# Pill_STM32F405.net
KiCad netlist of a schematic drawn in Altium Designer
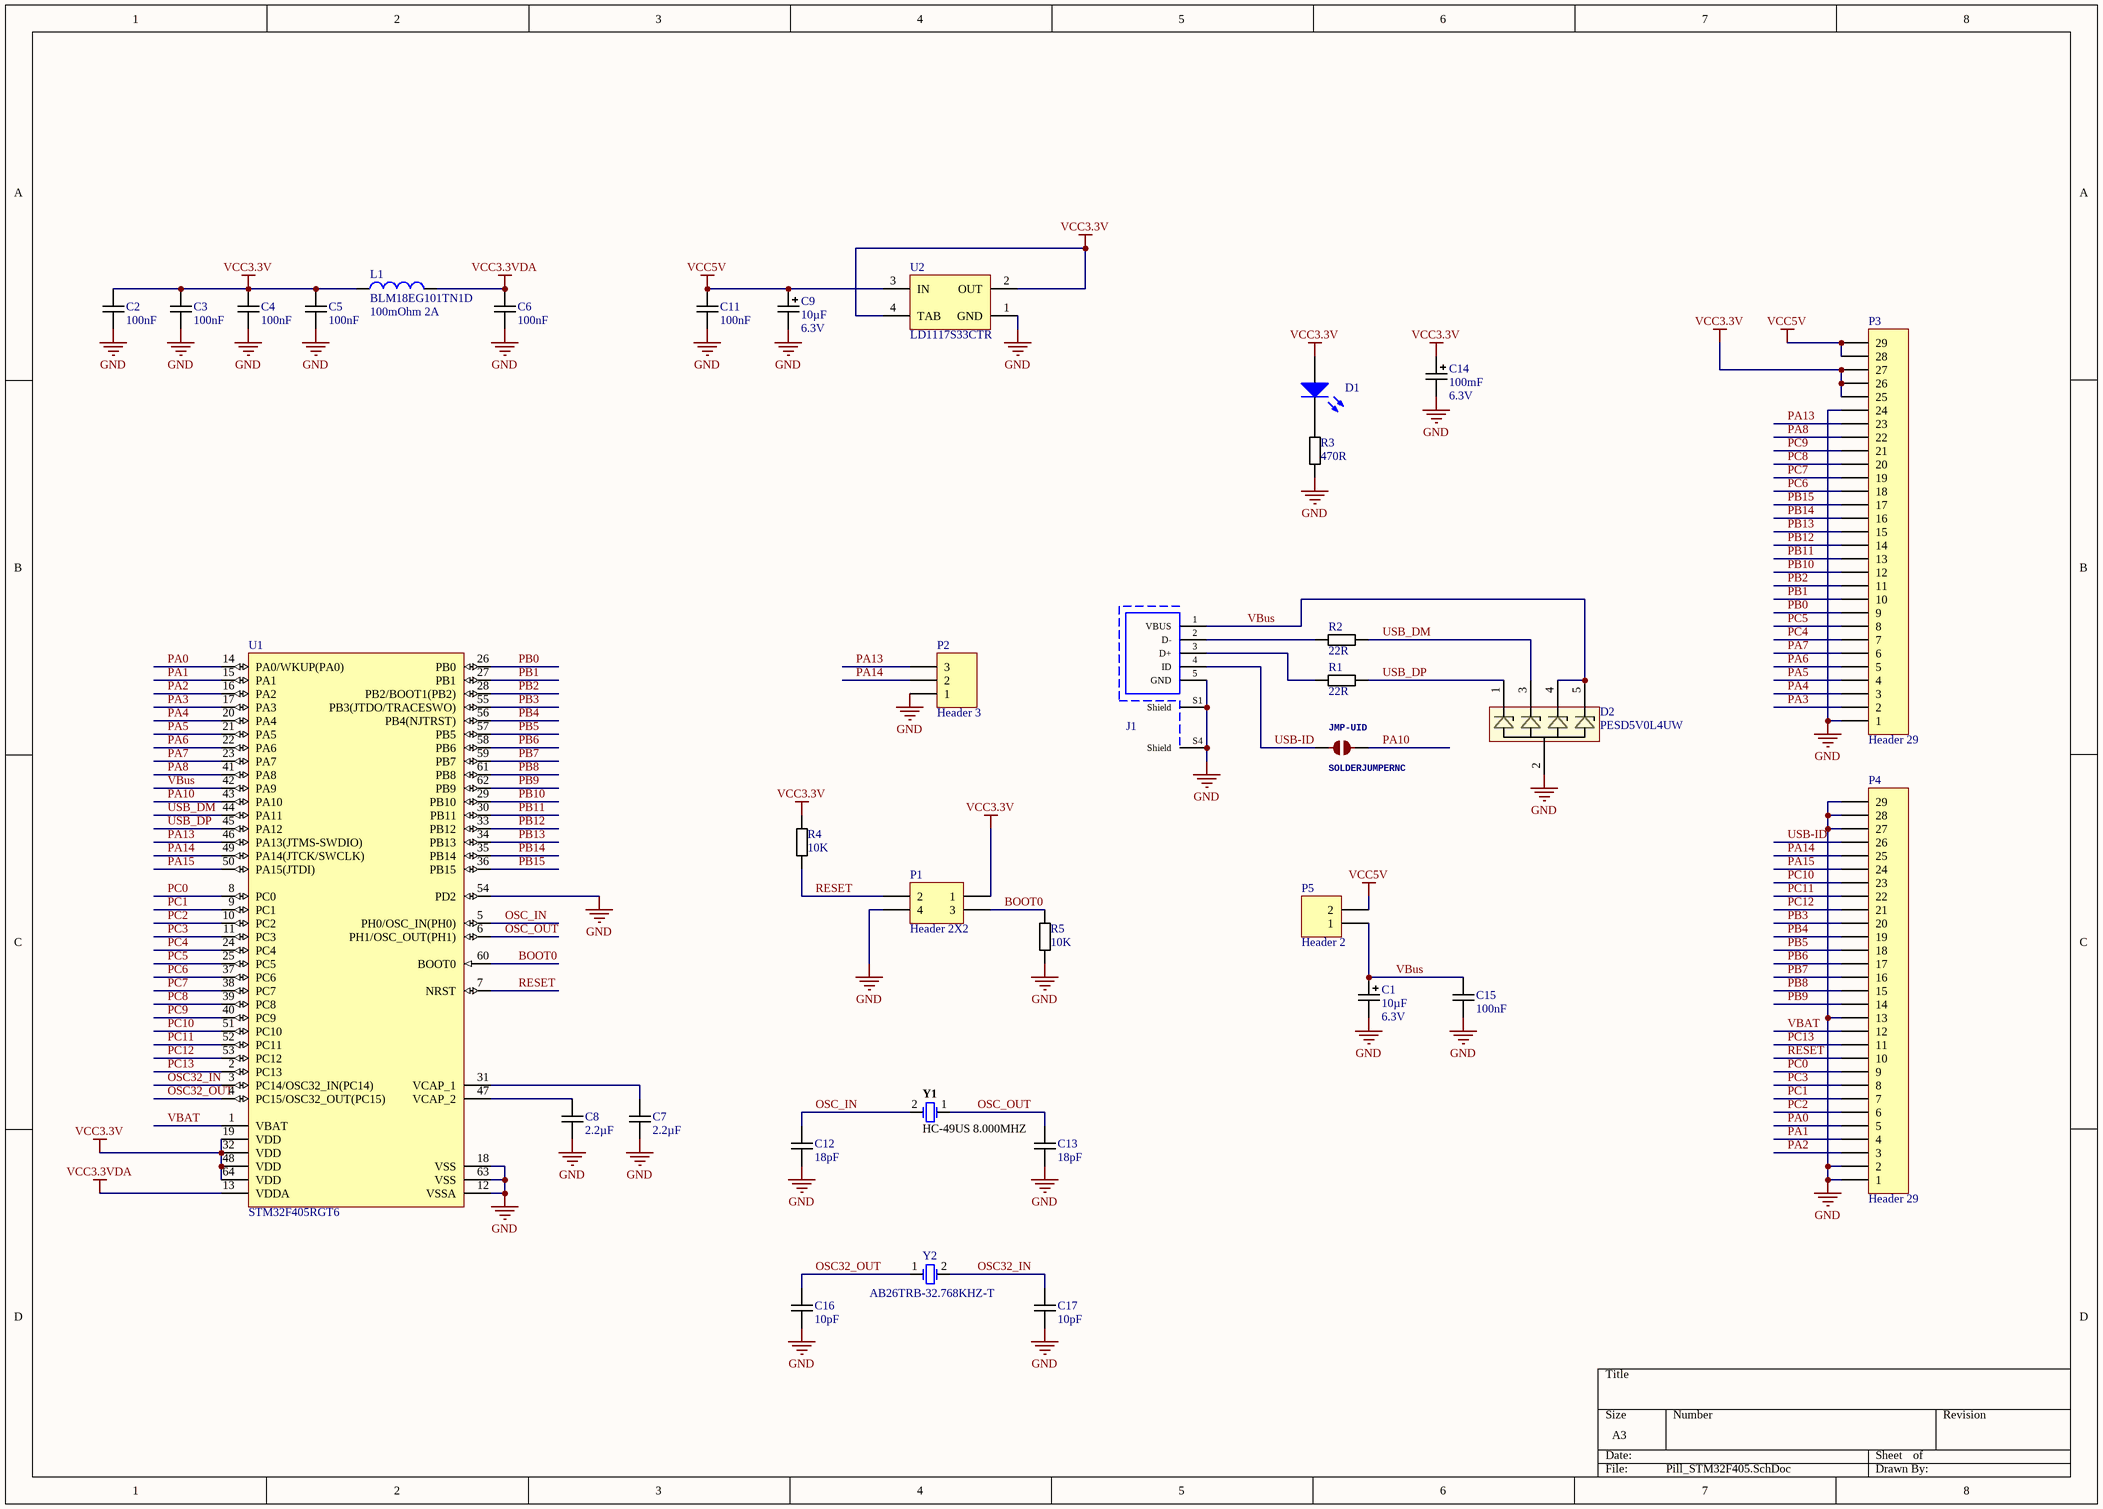
[diagram p0: Pill_STM32F405.SchDoc]

(export (version "E")
  (design (tool "Eeschema 10.0.6"))
  (components
    (comp (ref "C1")
      (value "10µF")
      (footprint "Capacitor_tantal_SMD:Body_A_M__CAPMP3216X18N")
      (description "10µF Molded Tantalum Capacitors 6.3V 1206 (3216 Metric) 4Ohm @ 100kHz")
      (fields
        (field (name "TOLERANCE") "5%")
        (field (name "MANUFACTURER") "AVX Corporation")
        (field (name "VOLTAGE - RATED") "6.3V")
      )
      (libsource (lib "Capacitors") (part "Capacitor Polarized"))
    )
    (comp (ref "C2")
      (value "100nF")
      (footprint "Pill_STM32F405:0603-CAP")
      (description "Capacitor 0603 100nF 50V")
      (fields (field (name "TOLERANCE") "±10%") (field (name "MANUFACTURER") "TDK Corporation"))
      (libsource (lib "Pill_STM32F405") (part "Capacitor_0603_100nF"))
    )
    (comp (ref "C3")
      (value "100nF")
      (footprint "Pill_STM32F405:0603-CAP")
      (description "Capacitor 0603 100nF 50V")
      (fields (field (name "TOLERANCE") "±10%") (field (name "MANUFACTURER") "TDK Corporation"))
      (libsource (lib "Pill_STM32F405") (part "Capacitor_0603_100nF"))
    )
    (comp (ref "C4")
      (value "100nF")
      (footprint "Pill_STM32F405:0603-CAP")
      (description "Capacitor 0603 100nF 50V")
      (fields (field (name "TOLERANCE") "±10%") (field (name "MANUFACTURER") "TDK Corporation"))
      (libsource (lib "Pill_STM32F405") (part "Capacitor_0603_100nF"))
    )
    (comp (ref "C5")
      (value "100nF")
      (footprint "Pill_STM32F405:0603-CAP")
      (description "Capacitor 0603 100nF 50V")
      (fields (field (name "TOLERANCE") "±10%") (field (name "MANUFACTURER") "TDK Corporation"))
      (libsource (lib "Pill_STM32F405") (part "Capacitor_0603_100nF"))
    )
    (comp (ref "C6")
      (value "100nF")
      (footprint "Pill_STM32F405:0603-CAP")
      (description "Capacitor 0603 100nF 50V")
      (fields (field (name "TOLERANCE") "±10%") (field (name "MANUFACTURER") "TDK Corporation"))
      (libsource (lib "Pill_STM32F405") (part "Capacitor_0603_100nF"))
    )
    (comp (ref "C7")
      (value "2.2µF")
      (footprint "Pill_STM32F405:0603-CAP")
      (description "Capacitor 0603 2.2µF 6.3V")
      (fields (field (name "TOLERANCE") "±10%") (field (name "MANUFACTURER") "TDK Corporation"))
      (libsource (lib "Pill_STM32F405") (part "Capacitor_0603_2.2µF"))
    )
    (comp (ref "C8")
      (value "2.2µF")
      (footprint "Pill_STM32F405:0603-CAP")
      (description "Capacitor 0603 2.2µF 6.3V")
      (fields (field (name "TOLERANCE") "±10%") (field (name "MANUFACTURER") "TDK Corporation"))
      (libsource (lib "Pill_STM32F405") (part "Capacitor_0603_2.2µF"))
    )
    (comp (ref "C9")
      (value "10µF")
      (footprint "Capacitor_tantal_SMD:Body_A_M__CAPMP3216X18N")
      (description "10µF Molded Tantalum Capacitors 6.3V 1206 (3216 Metric) 4Ohm @ 100kHz")
      (fields
        (field (name "TOLERANCE") "5%")
        (field (name "MANUFACTURER") "AVX Corporation")
        (field (name "VOLTAGE - RATED") "6.3V")
      )
      (libsource (lib "Capacitors") (part "Capacitor Polarized"))
    )
    (comp (ref "C11")
      (value "100nF")
      (footprint "Pill_STM32F405:0603-CAP")
      (description "Capacitor 0603 100nF 50V")
      (fields (field (name "TOLERANCE") "±10%") (field (name "MANUFACTURER") "TDK Corporation"))
      (libsource (lib "Pill_STM32F405") (part "Capacitor_0603_100nF"))
    )
    (comp (ref "C12")
      (value "18pF")
      (footprint "Pill_STM32F405:0603-CAP")
      (description "Capacitor 0603 18pF 100V")
      (fields (field (name "TOLERANCE") "±5%") (field (name "MANUFACTURER") "TDK Corporation"))
      (libsource (lib "Pill_STM32F405") (part "Capacitor_0603_18pF"))
    )
    (comp (ref "C13")
      (value "18pF")
      (footprint "Pill_STM32F405:0603-CAP")
      (description "Capacitor 0603 18pF 100V")
      (fields (field (name "TOLERANCE") "±5%") (field (name "MANUFACTURER") "TDK Corporation"))
      (libsource (lib "Pill_STM32F405") (part "Capacitor_0603_18pF"))
    )
    (comp (ref "C14")
      (value "100mF")
      (footprint "Capacitor_tantal_SMD:Body_C_L__CAPMP6032X28M")
      (description "100µF Molded Tantalum Capacitors 6.3V 2312 (6032 Metric) 900mOhm")
      (fields
        (field (name "TOLERANCE") "5%")
        (field (name "MANUFACTURER") "AVX Corporation")
        (field (name "VOLTAGE - RATED") "6.3V")
      )
      (libsource (lib "Capacitors") (part "Capacitor Polarized"))
    )
    (comp (ref "C15")
      (value "100nF")
      (footprint "Pill_STM32F405:0603-CAP")
      (description "Capacitor 0603 100nF 50V")
      (fields (field (name "TOLERANCE") "±10%") (field (name "MANUFACTURER") "TDK Corporation"))
      (libsource (lib "Pill_STM32F405") (part "Capacitor_0603_100nF"))
    )
    (comp (ref "C16")
      (value "10pF")
      (footprint "Pill_STM32F405:0603-CAP")
      (description "Capacitor 0603 10pF 100V")
      (fields (field (name "TOLERANCE") "±0.5%") (field (name "MANUFACTURER") "TDK Corporation"))
      (libsource (lib "Pill_STM32F405") (part "Capacitor_0603_10pF"))
    )
    (comp (ref "C17")
      (value "10pF")
      (footprint "Pill_STM32F405:0603-CAP")
      (description "Capacitor 0603 10pF 100V")
      (fields (field (name "TOLERANCE") "±0.5%") (field (name "MANUFACTURER") "TDK Corporation"))
      (libsource (lib "Pill_STM32F405") (part "Capacitor_0603_10pF"))
    )
    (comp (ref "D1")
      (value "LTST-C170KRKT")
      (footprint "LEDs:LED 0805 RED SMD")
      (description "LED RED  0805 SMD")
      (fields (field (name "MANUFACTURER") "Lite-On Inc."))
      (libsource (lib "LEDs") (part "LED 0805 RED SMD"))
    )
    (comp (ref "D2")
      (value "PESD5V0L4UW")
      (footprint "TVS_diodes:PESD5V0L4UW")
      (description "TVS DIODE 5V 13V 5TSSOP")
      (fields (field (name "MANUFACTURER") "Nexperia USA Inc."))
      (libsource (lib "TVS_diodes") (part "PESD5V0L4UW"))
    )
    (comp (ref "J1")
      (value "Micro USB 2.0 Type AB Receptacle")
      (footprint "Pill_STM32F405:USB-MICROB-SMD")
      (description "USB - micro B USB 2.0 Receptacle Connector 5 Position Surface Mount, Right Angle; Through Hole")
      (fields (field (name "MANUFACTURER") "KLS electronic co ltd"))
      (libsource (lib "USB") (part "KLS1-233-1-0-0-R"))
    )
    (comp (ref "JMP-UID")
      (value "SOLDERJUMPERNC")
      (footprint "SJ_2S")
      (fields (field (name "LIBRARYNAME") "stm32f4stamp"))
      (libsource (lib "stm32f4stamp") (part "SOLDERJUMPERNC"))
    )
    (comp (ref "L1")
      (value "BLM18EG101TN1D")
      (footprint "Inductor:BLM18")
      (description "100 Ohms @ 100MHz 1  Ferrite Bead 0603 (1608 Metric) 2A 45mOhm")
      (fields
        (field (name "MANUFACTURER") "Murata Electronics North America")
        (field (name "FEATURES") "100mOhm 2A")
      )
      (libsource (lib "Inductor") (part "BLM18EG101TN1D"))
    )
    (comp (ref "P1")
      (value "Header 2X2")
      (footprint "Headers_Male:HDR2X2")
      (description "CONN HEADER VERT 4POS 2.54MM")
      (fields (field (name "MANUFACTURER") "Sullins Connector Solutions"))
      (libsource (lib "Headers_Male") (part "Header 2X2"))
    )
    (comp (ref "P2")
      (value "Header 3")
      (footprint "Headers_Male:HDR1X3")
      (description "Header, 3-Pin 2.54mm")
      (fields (field (name "MANUFACTURER") "Samtec Inc."))
      (libsource (lib "Headers_Male") (part "Header 3"))
    )
    (comp (ref "P3")
      (value "Header 29")
      (footprint "Headers_Male:HDR1X29")
      (description "CONN HEADER VERT 29POS 2.54MM")
      (fields (field (name "MANUFACTURER") "Sullins Connector Solutions"))
      (libsource (lib "Headers_Male") (part "Header 29"))
    )
    (comp (ref "P4")
      (value "Header 29")
      (footprint "Headers_Male:HDR1X29")
      (description "CONN HEADER VERT 29POS 2.54MM")
      (fields (field (name "MANUFACTURER") "Sullins Connector Solutions"))
      (libsource (lib "Headers_Male") (part "Header 29"))
    )
    (comp (ref "P5")
      (value "Header 2")
      (footprint "Headers_Male:HDR1X2")
      (description "Header, 2-Pin 2.54mm")
      (fields (field (name "MANUFACTURER") "Samtec Inc."))
      (libsource (lib "Headers_Male") (part "Header 2"))
    )
    (comp (ref "R1")
      (value "22R")
      (footprint "Pill_STM32F405:0603-RES")
      (description "Resistors 0603 5%")
      (fields (field (name "TOLERANCE") "5%") (field (name "MANUFACTURER") "Panasonic Electronic Components"))
      (libsource (lib "Pill_STM32F405") (part "R_0603_22R_5%"))
    )
    (comp (ref "R2")
      (value "22R")
      (footprint "Pill_STM32F405:0603-RES")
      (description "Resistors 0603 5%")
      (fields (field (name "TOLERANCE") "5%") (field (name "MANUFACTURER") "Panasonic Electronic Components"))
      (libsource (lib "Pill_STM32F405") (part "R_0603_22R_5%"))
    )
    (comp (ref "R3")
      (value "470R")
      (footprint "Pill_STM32F405:0603-RES")
      (description "Resistors 0603 5%")
      (fields (field (name "TOLERANCE") "5%") (field (name "MANUFACTURER") "Panasonic Electronic Components"))
      (libsource (lib "Pill_STM32F405") (part "R_0603_470R_5%"))
    )
    (comp (ref "R4")
      (value "10K")
      (footprint "Pill_STM32F405:0603-RES")
      (description "Resistors 0603 5%")
      (fields (field (name "TOLERANCE") "5%") (field (name "MANUFACTURER") "Panasonic Electronic Components"))
      (libsource (lib "") (part "R_0603_10K_5%_1"))
    )
    (comp (ref "R5")
      (value "10K")
      (footprint "Pill_STM32F405:0603-RES")
      (description "Resistors 0603 5%")
      (fields (field (name "TOLERANCE") "5%") (field (name "MANUFACTURER") "Panasonic Electronic Components"))
      (libsource (lib "Pill_STM32F405") (part "R_0603_10K_5%"))
    )
    (comp (ref "U1")
      (value "STM32F405RGT6")
      (footprint "Pill_STM32F405:LQFP64")
      (fields (field (name "MANUFACTURER") "STMicroelectronics"))
      (libsource (lib "Pill_STM32F405") (part "STM32F405RGT6"))
    )
    (comp (ref "U2")
      (value "LD1117S33CTR")
      (footprint "MP04A_N")
      (description "IC REG LINEAR 3.3V 800MA SOT223")
      (fields (field (name "MANUFACTURER") "STMicroelectronics"))
      (libsource (lib "Altium Content Vault") (part "PM-REG-LM1086-SOT4"))
    )
    (comp (ref "Y1")
      (value "HC-49US 8.000MHZ")
      (footprint "CRYSTAL:JPY-HC-49US")
      (description "Crystal, 8 MHz,   -55°C ~ 125°C")
      (fields (field (name "MANUFACTURER") "ECS Inc."))
      (libsource (lib "CRYSTAL") (part "CMP-2100-03645-1_1"))
    )
    (comp (ref "Y2")
      (value "AB26TRB-32.768KHZ-T")
      (footprint "CRYSTAL:AB26TRB32768KHZT")
      (description "32.768kHz ±20ppm Crystal 12.5pF 50 kOhms Cylindrical Can, Radial")
      (fields (field (name "MANUFACTURER") "ABRACON") (field (name "TOLERANCE") "±20ppm"))
      (libsource (lib "CRYSTAL") (part "AB26TRB-32.768KHZ-T"))
    )
  )
  (nets
    (net (code "1") (name "/BOOT0") (class "Default")
      (node (ref "P1") (pin "3") (pinfunction "3_3") (pintype "passive"))
      (node (ref "R5") (pin "2") (pinfunction "2_2") (pintype "passive"))
      (node (ref "U1") (pin "60") (pinfunction "BOOT0_60") (pintype "input"))
    )
    (net (code "2") (name "/OSC32_IN") (class "Default")
      (node (ref "C17") (pin "2") (pinfunction "2_2") (pintype "passive"))
      (node (ref "U1") (pin "3") (pinfunction "PC14/OSC32_IN(PC14)_3") (pintype "bidirectional"))
      (node (ref "Y2") (pin "2") (pinfunction "2_2") (pintype "passive"))
    )
    (net (code "3") (name "/OSC32_OUT") (class "Default")
      (node (ref "C16") (pin "2") (pinfunction "2_2") (pintype "passive"))
      (node (ref "U1") (pin "4") (pinfunction "PC15/OSC32_OUT(PC15)_4") (pintype "bidirectional"))
      (node (ref "Y2") (pin "1") (pinfunction "1_1") (pintype "passive"))
    )
    (net (code "4") (name "/OSC_IN") (class "Default")
      (node (ref "C12") (pin "2") (pinfunction "2_2") (pintype "passive"))
      (node (ref "U1") (pin "5") (pinfunction "PH0/OSC_IN(PH0)_5") (pintype "bidirectional"))
      (node (ref "Y1") (pin "2") (pinfunction "2_2") (pintype "passive"))
    )
    (net (code "5") (name "/OSC_OUT") (class "Default")
      (node (ref "C13") (pin "2") (pinfunction "2_2") (pintype "passive"))
      (node (ref "U1") (pin "6") (pinfunction "PH1/OSC_OUT(PH1)_6") (pintype "bidirectional"))
      (node (ref "Y1") (pin "1") (pinfunction "1_1") (pintype "passive"))
    )
    (net (code "6") (name "/PA0") (class "Default")
      (node (ref "P4") (pin "5") (pinfunction "5_5") (pintype "passive"))
      (node (ref "U1") (pin "14") (pinfunction "PA0/WKUP(PA0)_14") (pintype "bidirectional"))
    )
    (net (code "7") (name "/PA1") (class "Default")
      (node (ref "P4") (pin "4") (pinfunction "4_4") (pintype "passive"))
      (node (ref "U1") (pin "15") (pinfunction "PA1_15") (pintype "bidirectional"))
    )
    (net (code "8") (name "/PA2") (class "Default")
      (node (ref "P4") (pin "3") (pinfunction "3_3") (pintype "passive"))
      (node (ref "U1") (pin "16") (pinfunction "PA2_16") (pintype "bidirectional"))
    )
    (net (code "9") (name "/PA3") (class "Default")
      (node (ref "P3") (pin "2") (pinfunction "2_2") (pintype "passive"))
      (node (ref "U1") (pin "17") (pinfunction "PA3_17") (pintype "bidirectional"))
    )
    (net (code "10") (name "/PA4") (class "Default")
      (node (ref "P3") (pin "3") (pinfunction "3_3") (pintype "passive"))
      (node (ref "U1") (pin "20") (pinfunction "PA4_20") (pintype "bidirectional"))
    )
    (net (code "11") (name "/PA5") (class "Default")
      (node (ref "P3") (pin "4") (pinfunction "4_4") (pintype "passive"))
      (node (ref "U1") (pin "21") (pinfunction "PA5_21") (pintype "bidirectional"))
    )
    (net (code "12") (name "/PA6") (class "Default")
      (node (ref "P3") (pin "5") (pinfunction "5_5") (pintype "passive"))
      (node (ref "U1") (pin "22") (pinfunction "PA6_22") (pintype "bidirectional"))
    )
    (net (code "13") (name "/PA7") (class "Default")
      (node (ref "P3") (pin "6") (pinfunction "6_6") (pintype "passive"))
      (node (ref "U1") (pin "23") (pinfunction "PA7_23") (pintype "bidirectional"))
    )
    (net (code "14") (name "/PA8") (class "Default")
      (node (ref "P3") (pin "22") (pinfunction "22_22") (pintype "passive"))
      (node (ref "U1") (pin "41") (pinfunction "PA8_41") (pintype "bidirectional"))
    )
    (net (code "15") (name "/PA10") (class "Default")
      (node (ref "JMP-UID") (pin "2") (pinfunction "2_2") (pintype "passive"))
      (node (ref "U1") (pin "43") (pinfunction "PA10_43") (pintype "bidirectional"))
    )
    (net (code "16") (name "/PA13") (class "Default")
      (node (ref "P2") (pin "3") (pinfunction "3_3") (pintype "passive"))
      (node (ref "P3") (pin "23") (pinfunction "23_23") (pintype "passive"))
      (node (ref "U1") (pin "46") (pinfunction "PA13(JTMS-SWDIO)_46") (pintype "bidirectional"))
    )
    (net (code "17") (name "/PA14") (class "Default")
      (node (ref "P2") (pin "2") (pinfunction "2_2") (pintype "passive"))
      (node (ref "P4") (pin "25") (pinfunction "25_25") (pintype "passive"))
      (node (ref "U1") (pin "49") (pinfunction "PA14(JTCK/SWCLK)_49") (pintype "bidirectional"))
    )
    (net (code "18") (name "/PA15") (class "Default")
      (node (ref "P4") (pin "24") (pinfunction "24_24") (pintype "passive"))
      (node (ref "U1") (pin "50") (pinfunction "PA15(JTDI)_50") (pintype "bidirectional"))
    )
    (net (code "19") (name "/PB0") (class "Default")
      (node (ref "P3") (pin "9") (pinfunction "9_9") (pintype "passive"))
      (node (ref "U1") (pin "26") (pinfunction "PB0_26") (pintype "bidirectional"))
    )
    (net (code "20") (name "/PB1") (class "Default")
      (node (ref "P3") (pin "10") (pinfunction "10_10") (pintype "passive"))
      (node (ref "U1") (pin "27") (pinfunction "PB1_27") (pintype "bidirectional"))
    )
    (net (code "21") (name "/PB2") (class "Default")
      (node (ref "P3") (pin "11") (pinfunction "11_11") (pintype "passive"))
      (node (ref "U1") (pin "28") (pinfunction "PB2/BOOT1(PB2)_28") (pintype "bidirectional"))
    )
    (net (code "22") (name "/PB3") (class "Default")
      (node (ref "P4") (pin "20") (pinfunction "20_20") (pintype "passive"))
      (node (ref "U1") (pin "55") (pinfunction "PB3(JTDO/TRACESWO)_55") (pintype "bidirectional"))
    )
    (net (code "23") (name "/PB4") (class "Default")
      (node (ref "P4") (pin "19") (pinfunction "19_19") (pintype "passive"))
      (node (ref "U1") (pin "56") (pinfunction "PB4(NJTRST)_56") (pintype "bidirectional"))
    )
    (net (code "24") (name "/PB5") (class "Default")
      (node (ref "P4") (pin "18") (pinfunction "18_18") (pintype "passive"))
      (node (ref "U1") (pin "57") (pinfunction "PB5_57") (pintype "bidirectional"))
    )
    (net (code "25") (name "/PB6") (class "Default")
      (node (ref "P4") (pin "17") (pinfunction "17_17") (pintype "passive"))
      (node (ref "U1") (pin "58") (pinfunction "PB6_58") (pintype "bidirectional"))
    )
    (net (code "26") (name "/PB7") (class "Default")
      (node (ref "P4") (pin "16") (pinfunction "16_16") (pintype "passive"))
      (node (ref "U1") (pin "59") (pinfunction "PB7_59") (pintype "bidirectional"))
    )
    (net (code "27") (name "/PB8") (class "Default")
      (node (ref "P4") (pin "15") (pinfunction "15_15") (pintype "passive"))
      (node (ref "U1") (pin "61") (pinfunction "PB8_61") (pintype "bidirectional"))
    )
    (net (code "28") (name "/PB9") (class "Default")
      (node (ref "P4") (pin "14") (pinfunction "14_14") (pintype "passive"))
      (node (ref "U1") (pin "62") (pinfunction "PB9_62") (pintype "bidirectional"))
    )
    (net (code "29") (name "/PB10") (class "Default")
      (node (ref "P3") (pin "12") (pinfunction "12_12") (pintype "passive"))
      (node (ref "U1") (pin "29") (pinfunction "PB10_29") (pintype "bidirectional"))
    )
    (net (code "30") (name "/PB11") (class "Default")
      (node (ref "P3") (pin "13") (pinfunction "13_13") (pintype "passive"))
      (node (ref "U1") (pin "30") (pinfunction "PB11_30") (pintype "bidirectional"))
    )
    (net (code "31") (name "/PB12") (class "Default")
      (node (ref "P3") (pin "14") (pinfunction "14_14") (pintype "passive"))
      (node (ref "U1") (pin "33") (pinfunction "PB12_33") (pintype "bidirectional"))
    )
    (net (code "32") (name "/PB13") (class "Default")
      (node (ref "P3") (pin "15") (pinfunction "15_15") (pintype "passive"))
      (node (ref "U1") (pin "34") (pinfunction "PB13_34") (pintype "bidirectional"))
    )
    (net (code "33") (name "/PB14") (class "Default")
      (node (ref "P3") (pin "16") (pinfunction "16_16") (pintype "passive"))
      (node (ref "U1") (pin "35") (pinfunction "PB14_35") (pintype "bidirectional"))
    )
    (net (code "34") (name "/PB15") (class "Default")
      (node (ref "P3") (pin "17") (pinfunction "17_17") (pintype "passive"))
      (node (ref "U1") (pin "36") (pinfunction "PB15_36") (pintype "bidirectional"))
    )
    (net (code "35") (name "/PC0") (class "Default")
      (node (ref "P4") (pin "9") (pinfunction "9_9") (pintype "passive"))
      (node (ref "U1") (pin "8") (pinfunction "PC0_8") (pintype "bidirectional"))
    )
    (net (code "36") (name "/PC1") (class "Default")
      (node (ref "P4") (pin "7") (pinfunction "7_7") (pintype "passive"))
      (node (ref "U1") (pin "9") (pinfunction "PC1_9") (pintype "bidirectional"))
    )
    (net (code "37") (name "/PC2") (class "Default")
      (node (ref "P4") (pin "6") (pinfunction "6_6") (pintype "passive"))
      (node (ref "U1") (pin "10") (pinfunction "PC2_10") (pintype "bidirectional"))
    )
    (net (code "38") (name "/PC3") (class "Default")
      (node (ref "P4") (pin "8") (pinfunction "8_8") (pintype "passive"))
      (node (ref "U1") (pin "11") (pinfunction "PC3_11") (pintype "bidirectional"))
    )
    (net (code "39") (name "/PC4") (class "Default")
      (node (ref "P3") (pin "7") (pinfunction "7_7") (pintype "passive"))
      (node (ref "U1") (pin "24") (pinfunction "PC4_24") (pintype "bidirectional"))
    )
    (net (code "40") (name "/PC5") (class "Default")
      (node (ref "P3") (pin "8") (pinfunction "8_8") (pintype "passive"))
      (node (ref "U1") (pin "25") (pinfunction "PC5_25") (pintype "bidirectional"))
    )
    (net (code "41") (name "/PC6") (class "Default")
      (node (ref "P3") (pin "18") (pinfunction "18_18") (pintype "passive"))
      (node (ref "U1") (pin "37") (pinfunction "PC6_37") (pintype "bidirectional"))
    )
    (net (code "42") (name "/PC7") (class "Default")
      (node (ref "P3") (pin "19") (pinfunction "19_19") (pintype "passive"))
      (node (ref "U1") (pin "38") (pinfunction "PC7_38") (pintype "bidirectional"))
    )
    (net (code "43") (name "/PC8") (class "Default")
      (node (ref "P3") (pin "20") (pinfunction "20_20") (pintype "passive"))
      (node (ref "U1") (pin "39") (pinfunction "PC8_39") (pintype "bidirectional"))
    )
    (net (code "44") (name "/PC9") (class "Default")
      (node (ref "P3") (pin "21") (pinfunction "21_21") (pintype "passive"))
      (node (ref "U1") (pin "40") (pinfunction "PC9_40") (pintype "bidirectional"))
    )
    (net (code "45") (name "/PC10") (class "Default")
      (node (ref "P4") (pin "23") (pinfunction "23_23") (pintype "passive"))
      (node (ref "U1") (pin "51") (pinfunction "PC10_51") (pintype "bidirectional"))
    )
    (net (code "46") (name "/PC11") (class "Default")
      (node (ref "P4") (pin "22") (pinfunction "22_22") (pintype "passive"))
      (node (ref "U1") (pin "52") (pinfunction "PC11_52") (pintype "bidirectional"))
    )
    (net (code "47") (name "/PC12") (class "Default")
      (node (ref "P4") (pin "21") (pinfunction "21_21") (pintype "passive"))
      (node (ref "U1") (pin "53") (pinfunction "PC12_53") (pintype "bidirectional"))
    )
    (net (code "48") (name "/PC13") (class "Default")
      (node (ref "P4") (pin "11") (pinfunction "11_11") (pintype "passive"))
      (node (ref "U1") (pin "2") (pinfunction "PC13_2") (pintype "bidirectional"))
    )
    (net (code "49") (name "/RESET") (class "Default")
      (node (ref "P1") (pin "2") (pinfunction "2_2") (pintype "passive"))
      (node (ref "P4") (pin "10") (pinfunction "10_10") (pintype "passive"))
      (node (ref "R4") (pin "2") (pinfunction "2_2") (pintype "passive"))
      (node (ref "U1") (pin "7") (pinfunction "NRST_7") (pintype "bidirectional"))
    )
    (net (code "50") (name "/USB-ID") (class "Default")
      (node (ref "J1") (pin "4") (pinfunction "ID_4") (pintype "passive"))
      (node (ref "JMP-UID") (pin "1") (pinfunction "1_1") (pintype "passive"))
      (node (ref "P4") (pin "26") (pinfunction "26_26") (pintype "passive"))
    )
    (net (code "51") (name "/USB_DM") (class "Default")
      (node (ref "D2") (pin "3") (pinfunction "3_3") (pintype "passive"))
      (node (ref "R2") (pin "1") (pinfunction "1_1") (pintype "passive"))
      (node (ref "U1") (pin "44") (pinfunction "PA11_44") (pintype "bidirectional"))
    )
    (net (code "52") (name "/USB_DP") (class "Default")
      (node (ref "D2") (pin "1") (pinfunction "1_1") (pintype "passive"))
      (node (ref "R1") (pin "1") (pinfunction "1_1") (pintype "passive"))
      (node (ref "U1") (pin "45") (pinfunction "PA12_45") (pintype "bidirectional"))
    )
    (net (code "53") (name "/VBAT") (class "Default")
      (node (ref "P4") (pin "12") (pinfunction "12_12") (pintype "passive"))
      (node (ref "U1") (pin "1") (pinfunction "VBAT_1") (pintype "power_in"))
    )
    (net (code "54") (name "/VBus") (class "Default")
      (node (ref "C1") (pin "1") (pinfunction "1_1") (pintype "passive"))
      (node (ref "C15") (pin "2") (pinfunction "2_2") (pintype "passive"))
      (node (ref "D2") (pin "4") (pinfunction "4_4") (pintype "passive"))
      (node (ref "D2") (pin "5") (pinfunction "5_5") (pintype "passive"))
      (node (ref "J1") (pin "1") (pinfunction "VBUS_1") (pintype "passive"))
      (node (ref "P5") (pin "1") (pinfunction "1_1") (pintype "passive"))
      (node (ref "U1") (pin "42") (pinfunction "PA9_42") (pintype "bidirectional"))
    )
    (net (code "55") (name "GND") (class "Default")
      (node (ref "C1") (pin "2") (pinfunction "2_2") (pintype "passive"))
      (node (ref "C11") (pin "1") (pinfunction "1_1") (pintype "passive"))
      (node (ref "C12") (pin "1") (pinfunction "1_1") (pintype "passive"))
      (node (ref "C13") (pin "1") (pinfunction "1_1") (pintype "passive"))
      (node (ref "C14") (pin "2") (pinfunction "2_2") (pintype "passive"))
      (node (ref "C15") (pin "1") (pinfunction "1_1") (pintype "passive"))
      (node (ref "C16") (pin "1") (pinfunction "1_1") (pintype "passive"))
      (node (ref "C17") (pin "1") (pinfunction "1_1") (pintype "passive"))
      (node (ref "C2") (pin "1") (pinfunction "1_1") (pintype "passive"))
      (node (ref "C3") (pin "1") (pinfunction "1_1") (pintype "passive"))
      (node (ref "C4") (pin "1") (pinfunction "1_1") (pintype "passive"))
      (node (ref "C5") (pin "1") (pinfunction "1_1") (pintype "passive"))
      (node (ref "C6") (pin "1") (pinfunction "1_1") (pintype "passive"))
      (node (ref "C7") (pin "1") (pinfunction "1_1") (pintype "passive"))
      (node (ref "C8") (pin "1") (pinfunction "1_1") (pintype "passive"))
      (node (ref "C9") (pin "2") (pinfunction "2_2") (pintype "passive"))
      (node (ref "D2") (pin "2") (pinfunction "2_2") (pintype "passive"))
      (node (ref "J1") (pin "5") (pinfunction "GND_5") (pintype "passive"))
      (node (ref "J1") (pin "S1") (pinfunction "Shield_S1") (pintype "passive"))
      (node (ref "J1") (pin "S4") (pinfunction "Shield_S4") (pintype "passive"))
      (node (ref "P1") (pin "4") (pinfunction "4_4") (pintype "passive"))
      (node (ref "P2") (pin "1") (pinfunction "1_1") (pintype "passive"))
      (node (ref "P3") (pin "1") (pinfunction "1_1") (pintype "passive"))
      (node (ref "P3") (pin "24") (pinfunction "24_24") (pintype "passive"))
      (node (ref "P4") (pin "1") (pinfunction "1_1") (pintype "passive"))
      (node (ref "P4") (pin "13") (pinfunction "13_13") (pintype "passive"))
      (node (ref "P4") (pin "2") (pinfunction "2_2") (pintype "passive"))
      (node (ref "P4") (pin "27") (pinfunction "27_27") (pintype "passive"))
      (node (ref "P4") (pin "28") (pinfunction "28_28") (pintype "passive"))
      (node (ref "P4") (pin "29") (pinfunction "29_29") (pintype "passive"))
      (node (ref "R3") (pin "1") (pinfunction "1_1") (pintype "passive"))
      (node (ref "R5") (pin "1") (pinfunction "1_1") (pintype "passive"))
      (node (ref "U1") (pin "12") (pinfunction "VSSA_12") (pintype "power_in"))
      (node (ref "U1") (pin "18") (pinfunction "VSS_18") (pintype "power_in"))
      (node (ref "U1") (pin "54") (pinfunction "PD2_54") (pintype "bidirectional"))
      (node (ref "U1") (pin "63") (pinfunction "VSS_63") (pintype "power_in"))
      (node (ref "U2") (pin "1") (pinfunction "GND_1") (pintype "power_in"))
    )
    (net (code "56") (name "Net-(D1-K)") (class "Default")
      (node (ref "D1") (pin "2") (pinfunction "K_2") (pintype "passive"))
      (node (ref "R3") (pin "2") (pinfunction "2_2") (pintype "passive"))
    )
    (net (code "57") (name "Net-(J1-D+)") (class "Default")
      (node (ref "J1") (pin "3") (pinfunction "D+_3") (pintype "passive"))
      (node (ref "R1") (pin "2") (pinfunction "2_2") (pintype "passive"))
    )
    (net (code "58") (name "Net-(J1-D-)") (class "Default")
      (node (ref "J1") (pin "2") (pinfunction "D-_2") (pintype "passive"))
      (node (ref "R2") (pin "2") (pinfunction "2_2") (pintype "passive"))
    )
    (net (code "59") (name "Net-(U1-VCAP_1)") (class "Default")
      (node (ref "C7") (pin "2") (pinfunction "2_2") (pintype "passive"))
      (node (ref "U1") (pin "31") (pinfunction "VCAP_1_31") (pintype "passive"))
    )
    (net (code "60") (name "Net-(U1-VCAP_2)") (class "Default")
      (node (ref "C8") (pin "2") (pinfunction "2_2") (pintype "passive"))
      (node (ref "U1") (pin "47") (pinfunction "VCAP_2_47") (pintype "passive"))
    )
    (net (code "61") (name "VCC3.3V") (class "Default")
      (node (ref "C14") (pin "1") (pinfunction "1_1") (pintype "passive"))
      (node (ref "C2") (pin "2") (pinfunction "2_2") (pintype "passive"))
      (node (ref "C3") (pin "2") (pinfunction "2_2") (pintype "passive"))
      (node (ref "C4") (pin "2") (pinfunction "2_2") (pintype "passive"))
      (node (ref "C5") (pin "2") (pinfunction "2_2") (pintype "passive"))
      (node (ref "D1") (pin "1") (pinfunction "A_1") (pintype "passive"))
      (node (ref "L1") (pin "1") (pinfunction "1_1") (pintype "passive"))
      (node (ref "P1") (pin "1") (pinfunction "1_1") (pintype "passive"))
      (node (ref "P3") (pin "25") (pinfunction "25_25") (pintype "passive"))
      (node (ref "P3") (pin "26") (pinfunction "26_26") (pintype "passive"))
      (node (ref "P3") (pin "27") (pinfunction "27_27") (pintype "passive"))
      (node (ref "R4") (pin "1") (pinfunction "1_1") (pintype "passive"))
      (node (ref "U1") (pin "19") (pinfunction "VDD_19") (pintype "power_in"))
      (node (ref "U1") (pin "32") (pinfunction "VDD_32") (pintype "power_in"))
      (node (ref "U1") (pin "48") (pinfunction "VDD_48") (pintype "power_in"))
      (node (ref "U1") (pin "64") (pinfunction "VDD_64") (pintype "power_in"))
      (node (ref "U2") (pin "2") (pinfunction "OUT_2") (pintype "power_in"))
      (node (ref "U2") (pin "4") (pinfunction "TAB_4") (pintype "power_in"))
    )
    (net (code "62") (name "VCC3.3VDA") (class "Default")
      (node (ref "C6") (pin "2") (pinfunction "2_2") (pintype "passive"))
      (node (ref "L1") (pin "2") (pinfunction "2_2") (pintype "passive"))
      (node (ref "U1") (pin "13") (pinfunction "VDDA_13") (pintype "power_in"))
    )
    (net (code "63") (name "VCC5V") (class "Default")
      (node (ref "C11") (pin "2") (pinfunction "2_2") (pintype "passive"))
      (node (ref "C9") (pin "1") (pinfunction "1_1") (pintype "passive"))
      (node (ref "P3") (pin "28") (pinfunction "28_28") (pintype "passive"))
      (node (ref "P3") (pin "29") (pinfunction "29_29") (pintype "passive"))
      (node (ref "P5") (pin "2") (pinfunction "2_2") (pintype "passive"))
      (node (ref "U2") (pin "3") (pinfunction "IN_3") (pintype "power_in"))
    )
  )
)
